# Precharge.net
KiCad netlist of a schematic drawn in Altium Designer
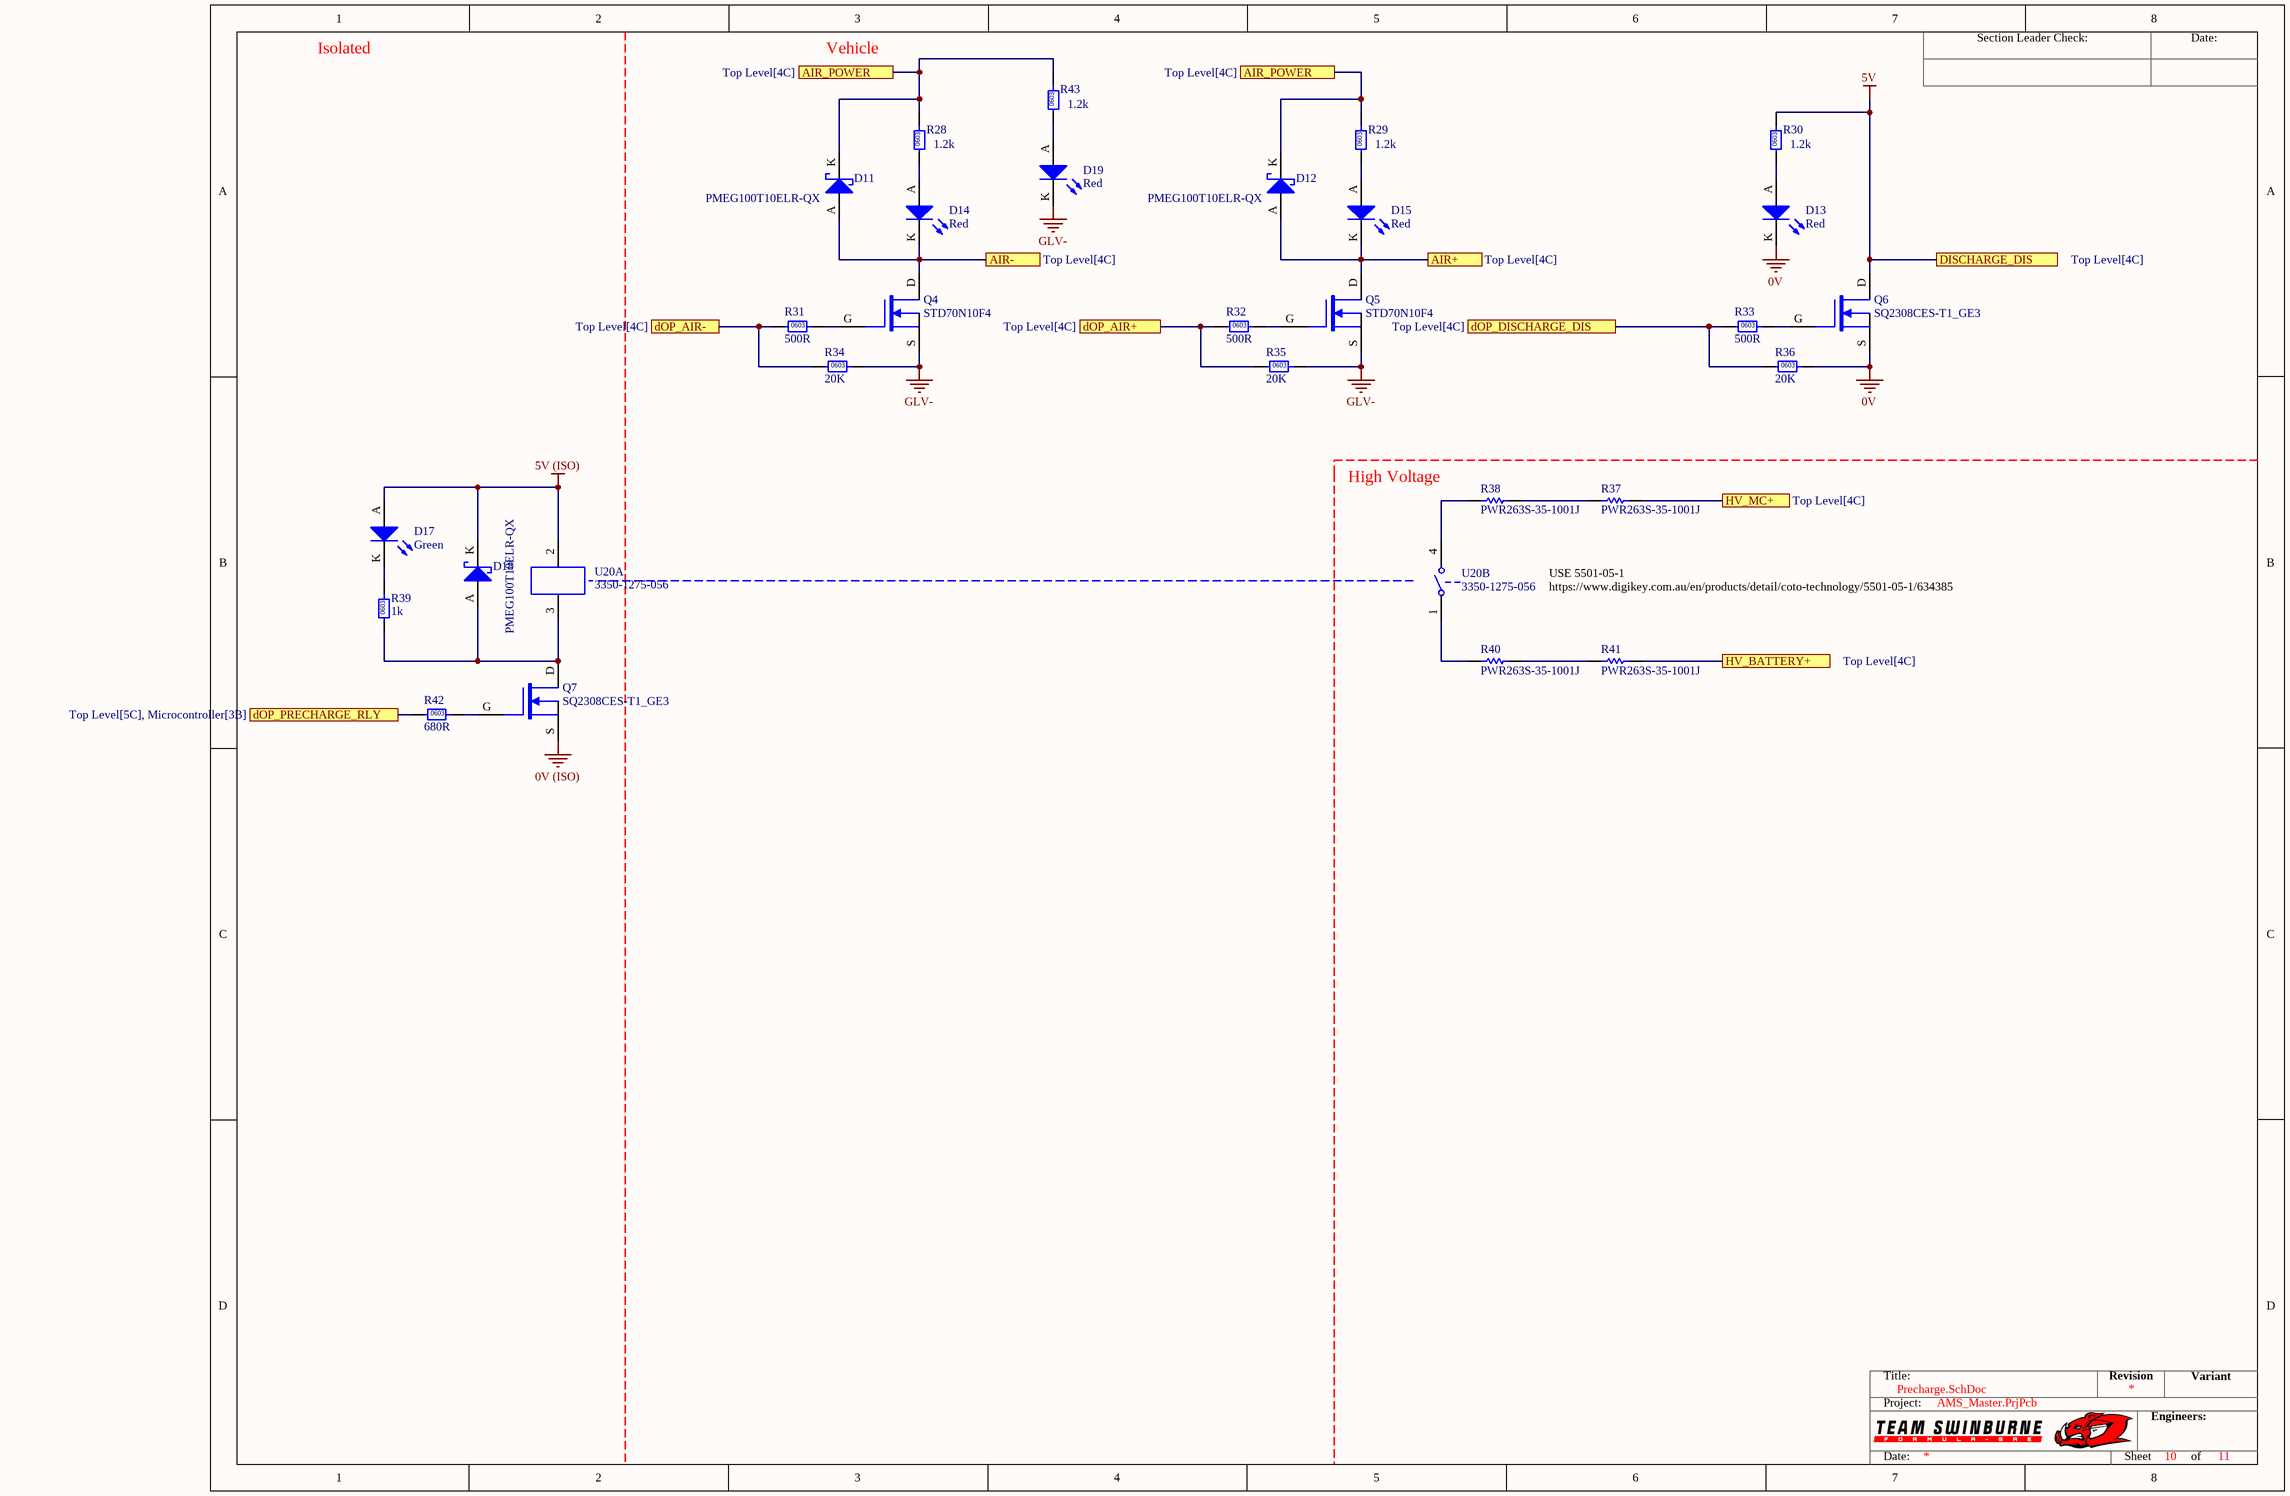
[diagram p0: Precharge.SchDoc]

(export (version "E")
  (design (tool "Eeschema 10.0.6"))
  (components
    (comp (ref "D11")
      (value "PMEG100T10ELR-QX")
      (footprint "NXP SOD123W")
      (fields
        (field (name "MANUFACTURER") "Nexperia USA Inc.")
        (field (name "DIGIKEY PART NUMBER") "1727-PMEG100T10ELR-QXCT-ND")
      )
      (libsource (lib "ts_standard_library") (part "Diode (Schottky)"))
    )
    (comp (ref "D12")
      (value "PMEG100T10ELR-QX")
      (footprint "NXP SOD123W")
      (fields
        (field (name "MANUFACTURER") "Nexperia USA Inc.")
        (field (name "DIGIKEY PART NUMBER") "1727-PMEG100T10ELR-QXCT-ND")
      )
      (libsource (lib "ts_standard_library") (part "Diode (Schottky)"))
    )
    (comp (ref "D13")
      (value "Red")
      (footprint "0805 LED")
      (description "Red LED Indication - Discrete 1.75V 0805 (2012 Metric)")
      (fields (field (name "PART NUMBER") "SML-210LTT86") (field (name "MANUFACTURER") "ROHM Semiconductor"))
      (libsource (lib "ts_standard_library") (part "LED"))
    )
    (comp (ref "D14")
      (value "Red")
      (footprint "0805 LED")
      (description "Red LED Indication - Discrete 1.75V 0805 (2012 Metric)")
      (fields (field (name "PART NUMBER") "SML-210LTT86") (field (name "MANUFACTURER") "ROHM Semiconductor"))
      (libsource (lib "ts_standard_library") (part "LED"))
    )
    (comp (ref "D15")
      (value "Red")
      (footprint "0805 LED")
      (description "Red LED Indication - Discrete 1.75V 0805 (2012 Metric)")
      (fields (field (name "PART NUMBER") "SML-210LTT86") (field (name "MANUFACTURER") "ROHM Semiconductor"))
      (libsource (lib "ts_standard_library") (part "LED"))
    )
    (comp (ref "D17")
      (value "Green")
      (footprint "0805 LED")
      (description "Green LED Indication - Discrete 1.75V 0805 (2012 Metric)")
      (fields (field (name "PART NUMBER") "SML-210FTT86") (field (name "MANUFACTURER") "ROHM Semiconductor"))
      (libsource (lib "ts_20-standard-library") (part "LED"))
    )
    (comp (ref "D18")
      (value "PMEG100T10ELR-QX")
      (footprint "NXP SOD123W")
      (fields
        (field (name "MANUFACTURER") "Nexperia USA Inc.")
        (field (name "DIGIKEY PART NUMBER") "1727-PMEG100T10ELR-QXCT-ND")
      )
      (libsource (lib "ts_standard_library") (part "Diode (Schottky)"))
    )
    (comp (ref "D19")
      (value "Red")
      (footprint "0805 LED")
      (description "Red LED Indication - Discrete 1.75V 0805 (2012 Metric)")
      (fields (field (name "PART NUMBER") "SML-210LTT86") (field (name "MANUFACTURER") "ROHM Semiconductor"))
      (libsource (lib "ts_standard_library") (part "LED"))
    )
    (comp (ref "Q4")
      (value "STD70N10F4")
      (footprint "STM TO-252 MOSFET")
      (description "N-Channel 100V 60A (Tc) 125W (Tc) Surface Mount DPAK")
      (fields
        (field (name "MANUFACTURER") "STMicroelectronics")
        (field (name "DIGIKEY PART NUMBER") "497-8806-2-ND")
        (field (name "PUBLISHER") "Altium Limited")
      )
      (libsource (lib "ts_standard_library") (part "MOSFET-N"))
    )
    (comp (ref "Q5")
      (value "STD70N10F4")
      (footprint "STM TO-252 MOSFET")
      (description "N-Channel 100V 60A (Tc) 125W (Tc) Surface Mount DPAK")
      (fields
        (field (name "MANUFACTURER") "STMicroelectronics")
        (field (name "DIGIKEY PART NUMBER") "497-8806-2-ND")
        (field (name "PUBLISHER") "Altium Limited")
      )
      (libsource (lib "ts_standard_library") (part "MOSFET-N"))
    )
    (comp (ref "Q6")
      (value "SQ2308CES-T1_GE3")
      (footprint "VSHY SOT-23-3")
      (description "MOSFET N-CH 60V 2.3A SOT23")
      (fields
        (field (name "MANUFACTURER") "Vishay Siliconix")
        (field (name "DIGIKEY PART NUMBER") "SQ2308CES-T1_GE3CT-ND")
        (field (name "PUBLISHER") "Altium Limited")
      )
      (libsource (lib "ts_standard_library") (part "MOSFET-N"))
    )
    (comp (ref "Q7")
      (value "SQ2308CES-T1_GE3")
      (footprint "VSHY SOT-23-3")
      (description "MOSFET N-CH 60V 2.3A SOT23")
      (fields
        (field (name "MANUFACTURER") "Vishay Siliconix")
        (field (name "DIGIKEY PART NUMBER") "SQ2308CES-T1_GE3CT-ND")
        (field (name "PUBLISHER") "Altium Limited")
      )
      (libsource (lib "ts_standard_library") (part "MOSFET-N"))
    )
    (comp (ref "R28")
      (value "1.2k")
      (footprint "0603")
      (fields
        (field (name "PART NUMBER") "RC0603JR-071K2L")
        (field (name "MANUFACTURER") "YAGEO")
        (field (name "TOLERANCE") "0.01")
      )
      (libsource (lib "ts_standard_library") (part "Resistor 0603"))
    )
    (comp (ref "R29")
      (value "1.2k")
      (footprint "0603")
      (fields
        (field (name "PART NUMBER") "RC0603JR-071K2L")
        (field (name "MANUFACTURER") "YAGEO")
        (field (name "TOLERANCE") "0.01")
      )
      (libsource (lib "ts_standard_library") (part "Resistor 0603"))
    )
    (comp (ref "R30")
      (value "1.2k")
      (footprint "0603")
      (fields
        (field (name "PART NUMBER") "RC0603JR-071K2L")
        (field (name "MANUFACTURER") "YAGEO")
        (field (name "TOLERANCE") "0.01")
      )
      (libsource (lib "ts_standard_library") (part "Resistor 0603"))
    )
    (comp (ref "R31")
      (value "500R")
      (footprint "0603")
      (fields
        (field (name "PART NUMBER") "RT0603BRD07500RL")
        (field (name "MANUFACTURER") "YAGEO")
        (field (name "TOLERANCE") "0.01")
      )
      (libsource (lib "ts_standard_library") (part "Resistor 0603"))
    )
    (comp (ref "R32")
      (value "500R")
      (footprint "0603")
      (fields
        (field (name "PART NUMBER") "RT0603BRD07500RL")
        (field (name "MANUFACTURER") "YAGEO")
        (field (name "TOLERANCE") "0.01")
      )
      (libsource (lib "ts_standard_library") (part "Resistor 0603"))
    )
    (comp (ref "R33")
      (value "500R")
      (footprint "0603")
      (fields
        (field (name "PART NUMBER") "RT0603BRD07500RL")
        (field (name "MANUFACTURER") "YAGEO")
        (field (name "TOLERANCE") "0.01")
      )
      (libsource (lib "ts_standard_library") (part "Resistor 0603"))
    )
    (comp (ref "R34")
      (value "20K")
      (footprint "0603")
      (fields
        (field (name "PART NUMBER") "RC0603FR-0720KL")
        (field (name "MANUFACTURER") "YAGEO")
        (field (name "TOLERANCE") "0.01")
      )
      (libsource (lib "ts_standard_library") (part "Resistor 0603"))
    )
    (comp (ref "R35")
      (value "20K")
      (footprint "0603")
      (fields
        (field (name "PART NUMBER") "RC0603FR-0720KL")
        (field (name "MANUFACTURER") "YAGEO")
        (field (name "TOLERANCE") "0.01")
      )
      (libsource (lib "ts_standard_library") (part "Resistor 0603"))
    )
    (comp (ref "R36")
      (value "20K")
      (footprint "0603")
      (fields
        (field (name "PART NUMBER") "RC0603FR-0720KL")
        (field (name "MANUFACTURER") "YAGEO")
        (field (name "TOLERANCE") "0.01")
      )
      (libsource (lib "ts_standard_library") (part "Resistor 0603"))
    )
    (comp (ref "R37")
      (value "PWR263S-35-1001J")
      (footprint "B TO-263")
      (fields
        (field (name "MANUFACTURER") "Bournes Inc")
        (field (name "TOLERANCE") "0.05")
        (field (name "DIGIKEY PART NUMBER") "PWR263S-35-1001J-ND")
      )
      (libsource (lib "Team Swinburne") (part "Resistor"))
    )
    (comp (ref "R38")
      (value "PWR263S-35-1001J")
      (footprint "B TO-263")
      (fields
        (field (name "MANUFACTURER") "Bournes Inc")
        (field (name "TOLERANCE") "0.05")
        (field (name "DIGIKEY PART NUMBER") "PWR263S-35-1001J-ND")
      )
      (libsource (lib "Team Swinburne") (part "Resistor"))
    )
    (comp (ref "R39")
      (value "1k")
      (footprint "0603")
      (fields
        (field (name "PART NUMBER") "RC0603FR-071KL")
        (field (name "MANUFACTURER") "YAGEO")
        (field (name "TOLERANCE") "0.01")
      )
      (libsource (lib "ts_standard_library") (part "Resistor 0603"))
    )
    (comp (ref "R40")
      (value "PWR263S-35-1001J")
      (footprint "B TO-263")
      (fields
        (field (name "MANUFACTURER") "Bournes Inc")
        (field (name "TOLERANCE") "0.05")
        (field (name "DIGIKEY PART NUMBER") "PWR263S-35-1001J-ND")
      )
      (libsource (lib "Team Swinburne") (part "Resistor"))
    )
    (comp (ref "R41")
      (value "PWR263S-35-1001J")
      (footprint "B TO-263")
      (fields
        (field (name "MANUFACTURER") "Bournes Inc")
        (field (name "TOLERANCE") "0.05")
        (field (name "DIGIKEY PART NUMBER") "PWR263S-35-1001J-ND")
      )
      (libsource (lib "Team Swinburne") (part "Resistor"))
    )
    (comp (ref "R42")
      (value "680R")
      (footprint "0603")
      (fields
        (field (name "PART NUMBER") "RC0603JR-13680RL")
        (field (name "MANUFACTURER") "YAGEO")
        (field (name "TOLERANCE") "0.01")
      )
      (libsource (lib "ts_standard_library") (part "Resistor 0603"))
    )
    (comp (ref "R43")
      (value "1.2k")
      (footprint "0603")
      (fields
        (field (name "PART NUMBER") "RC0603JR-071K2L")
        (field (name "MANUFACTURER") "YAGEO")
        (field (name "TOLERANCE") "0.01")
      )
      (libsource (lib "ts_standard_library") (part "Resistor 0603"))
    )
    (comp (ref "U20")
      (value "3350-1275-056")
      (footprint "CI SPST")
      (description "RELAY REED HV SPST 200W 3A 5V (NO)")
      (fields
        (field (name "MANUFACTURER") "Comus International")
        (field (name "DIGIKEY PART NUMBER") "1835-1036-ND")
      )
      (libsource (lib "") (part "3350-1275-056_1"))
    )
  )
  (nets
    (net (code "1") (name "/AIR+") (class "Default")
      (node (ref "D12") (pin "A") (pinfunction "A_A") (pintype "passive"))
      (node (ref "D15") (pin "K") (pinfunction "K_K") (pintype "passive"))
      (node (ref "Q5") (pin "D") (pinfunction "D_D") (pintype "passive"))
    )
    (net (code "2") (name "/AIR-") (class "Default")
      (node (ref "D11") (pin "A") (pinfunction "A_A") (pintype "passive"))
      (node (ref "D14") (pin "K") (pinfunction "K_K") (pintype "passive"))
      (node (ref "Q4") (pin "D") (pinfunction "D_D") (pintype "passive"))
    )
    (net (code "3") (name "/AIR_POWER") (class "Default")
      (node (ref "D11") (pin "K") (pinfunction "K_K") (pintype "passive"))
      (node (ref "D12") (pin "K") (pinfunction "K_K") (pintype "passive"))
      (node (ref "R28") (pin "2") (pinfunction "2_2") (pintype "passive"))
      (node (ref "R29") (pin "2") (pinfunction "2_2") (pintype "passive"))
      (node (ref "R43") (pin "2") (pinfunction "2_2") (pintype "passive"))
    )
    (net (code "4") (name "/HV_BATTERY+") (class "Default")
      (node (ref "R41") (pin "2") (pinfunction "2_2") (pintype "passive"))
    )
    (net (code "5") (name "/HV_MC+") (class "Default")
      (node (ref "R37") (pin "1") (pinfunction "1_1") (pintype "passive"))
    )
    (net (code "6") (name "/dOP_AIR+") (class "Default")
      (node (ref "R32") (pin "1") (pinfunction "1_1") (pintype "passive"))
      (node (ref "R35") (pin "1") (pinfunction "1_1") (pintype "passive"))
    )
    (net (code "7") (name "/dOP_AIR-") (class "Default")
      (node (ref "R31") (pin "1") (pinfunction "1_1") (pintype "passive"))
      (node (ref "R34") (pin "1") (pinfunction "1_1") (pintype "passive"))
    )
    (net (code "8") (name "/dOP_DISCHARGE_DIS") (class "Default")
      (node (ref "R33") (pin "1") (pinfunction "1_1") (pintype "passive"))
      (node (ref "R36") (pin "1") (pinfunction "1_1") (pintype "passive"))
    )
    (net (code "9") (name "/dOP_PRECHARGE_RLY") (class "Default")
      (node (ref "R42") (pin "1") (pinfunction "1_1") (pintype "passive"))
    )
    (net (code "10") (name "0V") (class "Default")
      (node (ref "D13") (pin "K") (pinfunction "K_K") (pintype "passive"))
      (node (ref "Q6") (pin "S") (pinfunction "S_S") (pintype "passive"))
      (node (ref "R36") (pin "2") (pinfunction "2_2") (pintype "passive"))
    )
    (net (code "11") (name "0V (ISO)") (class "Default")
      (node (ref "Q7") (pin "S") (pinfunction "S_S") (pintype "passive"))
    )
    (net (code "12") (name "5V") (class "Default")
      (node (ref "Q6") (pin "D") (pinfunction "D_D") (pintype "passive"))
      (node (ref "R30") (pin "2") (pinfunction "2_2") (pintype "passive"))
    )
    (net (code "13") (name "5V (ISO)") (class "Default")
      (node (ref "D17") (pin "A") (pinfunction "A_A") (pintype "passive"))
      (node (ref "D18") (pin "K") (pinfunction "K_K") (pintype "passive"))
      (node (ref "U20") (pin "2") (pinfunction "2_2") (pintype "passive"))
    )
    (net (code "14") (name "GLV-") (class "Default")
      (node (ref "D19") (pin "K") (pinfunction "K_K") (pintype "passive"))
      (node (ref "Q4") (pin "S") (pinfunction "S_S") (pintype "passive"))
      (node (ref "Q5") (pin "S") (pinfunction "S_S") (pintype "passive"))
      (node (ref "R34") (pin "2") (pinfunction "2_2") (pintype "passive"))
      (node (ref "R35") (pin "2") (pinfunction "2_2") (pintype "passive"))
    )
    (net (code "15") (name "Net-(D13-PadA)") (class "Default")
      (node (ref "D13") (pin "A") (pinfunction "A_A") (pintype "passive"))
      (node (ref "R30") (pin "1") (pinfunction "1_1") (pintype "passive"))
    )
    (net (code "16") (name "Net-(D14-PadA)") (class "Default")
      (node (ref "D14") (pin "A") (pinfunction "A_A") (pintype "passive"))
      (node (ref "R28") (pin "1") (pinfunction "1_1") (pintype "passive"))
    )
    (net (code "17") (name "Net-(D15-PadA)") (class "Default")
      (node (ref "D15") (pin "A") (pinfunction "A_A") (pintype "passive"))
      (node (ref "R29") (pin "1") (pinfunction "1_1") (pintype "passive"))
    )
    (net (code "18") (name "Net-(D17-PadK)") (class "Default")
      (node (ref "D17") (pin "K") (pinfunction "K_K") (pintype "passive"))
      (node (ref "R39") (pin "2") (pinfunction "2_2") (pintype "passive"))
    )
    (net (code "19") (name "Net-(D18-PadA)") (class "Default")
      (node (ref "D18") (pin "A") (pinfunction "A_A") (pintype "passive"))
      (node (ref "Q7") (pin "D") (pinfunction "D_D") (pintype "passive"))
      (node (ref "R39") (pin "1") (pinfunction "1_1") (pintype "passive"))
      (node (ref "U20") (pin "3") (pinfunction "3_3") (pintype "passive"))
    )
    (net (code "20") (name "Net-(D19-PadA)") (class "Default")
      (node (ref "D19") (pin "A") (pinfunction "A_A") (pintype "passive"))
      (node (ref "R43") (pin "1") (pinfunction "1_1") (pintype "passive"))
    )
    (net (code "21") (name "Net-(Q4-PadG)") (class "Default")
      (node (ref "Q4") (pin "G") (pinfunction "G_G") (pintype "passive"))
      (node (ref "R31") (pin "2") (pinfunction "2_2") (pintype "passive"))
    )
    (net (code "22") (name "Net-(Q5-PadG)") (class "Default")
      (node (ref "Q5") (pin "G") (pinfunction "G_G") (pintype "passive"))
      (node (ref "R32") (pin "2") (pinfunction "2_2") (pintype "passive"))
    )
    (net (code "23") (name "Net-(Q6-PadG)") (class "Default")
      (node (ref "Q6") (pin "G") (pinfunction "G_G") (pintype "passive"))
      (node (ref "R33") (pin "2") (pinfunction "2_2") (pintype "passive"))
    )
    (net (code "24") (name "Net-(Q7-PadG)") (class "Default")
      (node (ref "Q7") (pin "G") (pinfunction "G_G") (pintype "passive"))
      (node (ref "R42") (pin "2") (pinfunction "2_2") (pintype "passive"))
    )
    (net (code "25") (name "Net-(R37-Pad2)") (class "Default")
      (node (ref "R37") (pin "2") (pinfunction "2_2") (pintype "passive"))
      (node (ref "R38") (pin "1") (pinfunction "1_1") (pintype "passive"))
    )
    (net (code "26") (name "Net-(R38-Pad2)") (class "Default")
      (node (ref "R38") (pin "2") (pinfunction "2_2") (pintype "passive"))
      (node (ref "U20") (pin "4") (pinfunction "4_4") (pintype "passive"))
    )
    (net (code "27") (name "Net-(R40-Pad1)") (class "Default")
      (node (ref "R40") (pin "1") (pinfunction "1_1") (pintype "passive"))
      (node (ref "U20") (pin "1") (pinfunction "1_1") (pintype "passive"))
    )
    (net (code "28") (name "Net-(R40-Pad2)") (class "Default")
      (node (ref "R40") (pin "2") (pinfunction "2_2") (pintype "passive"))
      (node (ref "R41") (pin "1") (pinfunction "1_1") (pintype "passive"))
    )
  )
)
